# SCH_sweeping-mesuring-device_V2_2022-12-.net
KiCad netlist of a schematic drawn in EasyEDA
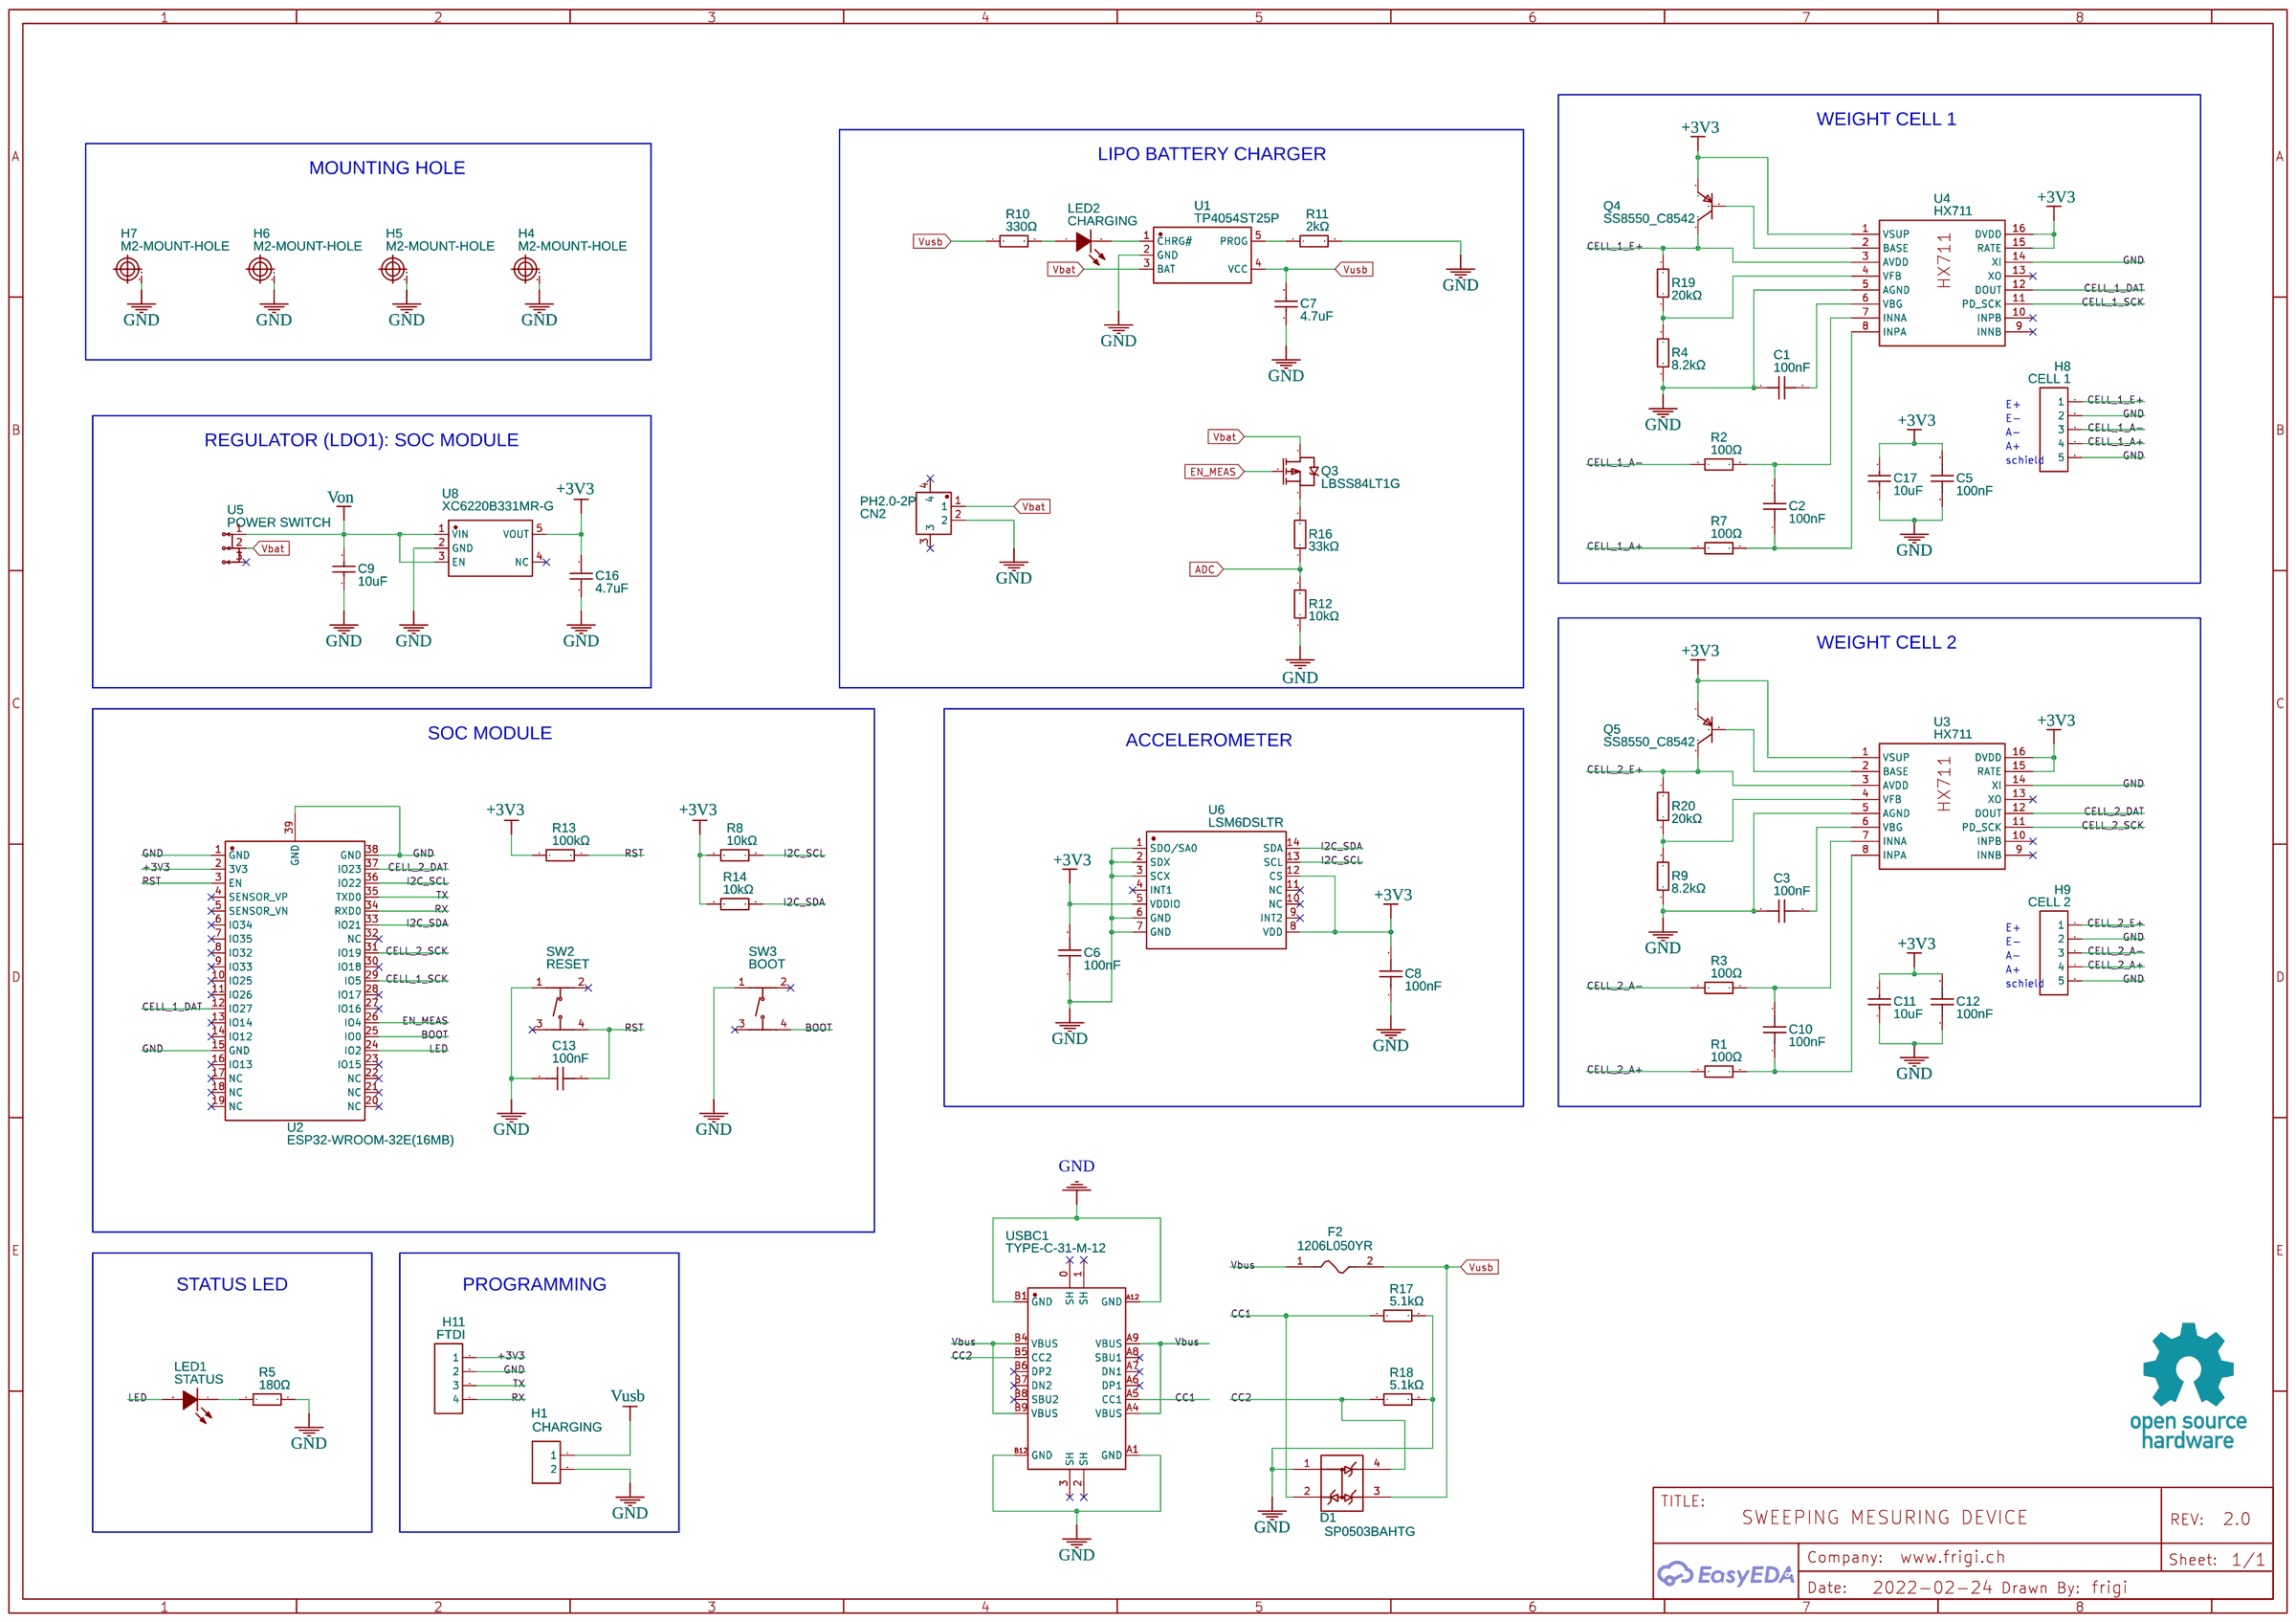
[diagram p0: schematic sheet]

(export (version "E")
  (design (tool "Eeschema 10.0.6"))
  (components
    (comp (ref "C1")
      (value "100nF")
      (fields
        (field (name "BOM_Manufacturer Part") "CC0603KRX7R9BB104")
        (field (name "BOM_Supplier Part") "C14663")
      )
      (libsource (lib "") (part "CC0603KRX7R9BB104_1"))
    )
    (comp (ref "C2")
      (value "100nF")
      (fields
        (field (name "BOM_Manufacturer Part") "CC0603KRX7R9BB104")
        (field (name "BOM_Supplier Part") "C14663")
      )
      (libsource (lib "") (part "CC0603KRX7R9BB104"))
    )
    (comp (ref "C3")
      (value "100nF")
      (fields
        (field (name "BOM_Manufacturer Part") "CC0603KRX7R9BB104")
        (field (name "BOM_Supplier Part") "C14663")
      )
      (libsource (lib "") (part "CC0603KRX7R9BB104_1"))
    )
    (comp (ref "C5")
      (value "100nF")
      (fields
        (field (name "BOM_Manufacturer Part") "CC0603KRX7R9BB104")
        (field (name "BOM_Supplier Part") "C14663")
      )
      (libsource (lib "") (part "CC0603KRX7R9BB104"))
    )
    (comp (ref "C6")
      (value "100nF")
      (fields
        (field (name "BOM_Manufacturer Part") "CC0603KRX7R9BB104")
        (field (name "BOM_Supplier Part") "C14663")
      )
      (libsource (lib "") (part "CC0603KRX7R9BB104"))
    )
    (comp (ref "C7")
      (value "4.7uF")
      (fields
        (field (name "BOM_Manufacturer Part") "CL21A475KAQNNNE")
        (field (name "BOM_Supplier Part") "C1779")
      )
      (libsource (lib "") (part "CL21A475KAQNNNE"))
    )
    (comp (ref "C8")
      (value "100nF")
      (fields
        (field (name "BOM_Manufacturer Part") "CC0603KRX7R9BB104")
        (field (name "BOM_Supplier Part") "C14663")
      )
      (libsource (lib "") (part "CC0603KRX7R9BB104"))
    )
    (comp (ref "C9")
      (value "10uF")
      (fields
        (field (name "BOM_Manufacturer Part") "CL21A106KAYNNNE")
        (field (name "BOM_Supplier Part") "C15850")
      )
      (libsource (lib "") (part "CL21A106KAYNNNE"))
    )
    (comp (ref "C10")
      (value "100nF")
      (fields
        (field (name "BOM_Manufacturer Part") "CC0603KRX7R9BB104")
        (field (name "BOM_Supplier Part") "C14663")
      )
      (libsource (lib "") (part "CC0603KRX7R9BB104"))
    )
    (comp (ref "C11")
      (value "10uF")
      (fields
        (field (name "BOM_Manufacturer Part") "CL21A106KAYNNNE")
        (field (name "BOM_Supplier Part") "C15850")
      )
      (libsource (lib "") (part "CL21A106KAYNNNE"))
    )
    (comp (ref "C12")
      (value "100nF")
      (fields
        (field (name "BOM_Manufacturer Part") "CC0603KRX7R9BB104")
        (field (name "BOM_Supplier Part") "C14663")
      )
      (libsource (lib "") (part "CC0603KRX7R9BB104"))
    )
    (comp (ref "C13")
      (value "100nF")
      (fields
        (field (name "BOM_Manufacturer Part") "CC0603KRX7R9BB104")
        (field (name "BOM_Supplier Part") "C14663")
      )
      (libsource (lib "") (part "CC0603KRX7R9BB104_1"))
    )
    (comp (ref "C16")
      (value "4.7uF")
      (fields
        (field (name "BOM_Manufacturer Part") "CL21A475KAQNNNE")
        (field (name "BOM_Supplier Part") "C1779")
      )
      (libsource (lib "") (part "CL21A475KAQNNNE"))
    )
    (comp (ref "C17")
      (value "10uF")
      (fields
        (field (name "BOM_Manufacturer Part") "CL21A106KAYNNNE")
        (field (name "BOM_Supplier Part") "C15850")
      )
      (libsource (lib "") (part "CL21A106KAYNNNE"))
    )
    (comp (ref "CN2")
      (value "PH2.0-2P")
      (fields (field (name "BOM_Supplier Part") "C64658"))
      (libsource (lib "") (part "PH2.0-2P"))
    )
    (comp (ref "D1")
      (value "SP0503BAHTG")
      (fields (field (name "BOM_Supplier Part") "C7074"))
      (libsource (lib "") (part "SP0503BAHTG"))
    )
    (comp (ref "F2")
      (value "1206L050YR")
      (fields (field (name "BOM_Manufacturer Part") "nSMD050") (field (name "BOM_Supplier Part") "C69688"))
      (libsource (lib "") (part "nSMD050"))
    )
    (comp (ref "H1")
      (value "CHARGING")
      (fields (field (name "BOM_Supplier Part") "C49661"))
      (libsource (lib "") (part "HDR-F-2.54_1x2"))
    )
    (comp (ref "H4") (value "M2-MOUNT-HOLE") (libsource (lib "") (part "M2-MOUNT-HOLE")))
    (comp (ref "H5") (value "M2-MOUNT-HOLE") (libsource (lib "") (part "M2-MOUNT-HOLE")))
    (comp (ref "H6") (value "M2-MOUNT-HOLE") (libsource (lib "") (part "M2-MOUNT-HOLE")))
    (comp (ref "H7") (value "M2-MOUNT-HOLE") (libsource (lib "") (part "M2-MOUNT-HOLE")))
    (comp (ref "H8")
      (value "CELL 1")
      (fields (field (name "BOM_Supplier Part") "C50950"))
      (libsource (lib "") (part "HDR-F-2.54_1x5"))
    )
    (comp (ref "H9")
      (value "CELL 2")
      (fields (field (name "BOM_Supplier Part") "C50950"))
      (libsource (lib "") (part "HDR-F-2.54_1x5"))
    )
    (comp (ref "H11")
      (value "FTDI")
      (fields (field (name "BOM_Supplier Part") "C225501"))
      (libsource (lib "") (part "HDR-F-2.54_1x4"))
    )
    (comp (ref "LED1")
      (value "STATUS")
      (fields
        (field (name "BOM_Manufacturer Part") "KT-0805黄灯 (SMT业务专用)")
        (field (name "BOM_Supplier Part") "C2296")
      )
      (libsource (lib "") (part "17-21SUYC/TR8"))
    )
    (comp (ref "LED2")
      (value "CHARGING")
      (fields
        (field (name "BOM_Manufacturer Part") "KT-0805黄灯 (SMT业务专用)")
        (field (name "BOM_Supplier Part") "C2296")
      )
      (libsource (lib "") (part "17-21SUYC/TR8"))
    )
    (comp (ref "Q3")
      (value "LBSS84LT1G")
      (fields (field (name "BOM_Supplier Part") "C8492"))
      (libsource (lib "") (part "LBSS84LT1G"))
    )
    (comp (ref "Q4")
      (value "SS8550_C8542")
      (fields (field (name "BOM_Manufacturer Part") "SS8550 Y2") (field (name "BOM_Supplier Part") "C8542"))
      (libsource (lib "") (part "SS8550_C8542"))
    )
    (comp (ref "Q5")
      (value "SS8550_C8542")
      (fields (field (name "BOM_Manufacturer Part") "SS8550 Y2") (field (name "BOM_Supplier Part") "C8542"))
      (libsource (lib "") (part "SS8550_C8542"))
    )
    (comp (ref "R1")
      (value "100Ω")
      (fields
        (field (name "BOM_Manufacturer Part") "0402WGF1000TCE")
        (field (name "BOM_Supplier Part") "C25076")
      )
      (libsource (lib "") (part "0402WGF1000TCE"))
    )
    (comp (ref "R2")
      (value "100Ω")
      (fields
        (field (name "BOM_Manufacturer Part") "0402WGF1000TCE")
        (field (name "BOM_Supplier Part") "C25076")
      )
      (libsource (lib "") (part "0402WGF1000TCE"))
    )
    (comp (ref "R3")
      (value "100Ω")
      (fields
        (field (name "BOM_Manufacturer Part") "0402WGF1000TCE")
        (field (name "BOM_Supplier Part") "C25076")
      )
      (libsource (lib "") (part "0402WGF1000TCE"))
    )
    (comp (ref "R4")
      (value "8.2kΩ")
      (fields
        (field (name "BOM_Manufacturer Part") "0603WAF8201T5E")
        (field (name "BOM_Supplier Part") "C25981")
      )
      (libsource (lib "") (part "0603WAF8201T5E"))
    )
    (comp (ref "R5")
      (value "180Ω")
      (fields
        (field (name "BOM_Manufacturer Part") "0603WAF1800T5E")
        (field (name "BOM_Supplier Part") "C22828")
      )
      (libsource (lib "") (part "0603WAF1800T5E"))
    )
    (comp (ref "R7")
      (value "100Ω")
      (fields
        (field (name "BOM_Manufacturer Part") "0402WGF1000TCE")
        (field (name "BOM_Supplier Part") "C25076")
      )
      (libsource (lib "") (part "0402WGF1000TCE"))
    )
    (comp (ref "R8")
      (value "10kΩ")
      (fields
        (field (name "BOM_Manufacturer Part") "0603WAF1002T5E")
        (field (name "BOM_Supplier Part") "C25804")
      )
      (libsource (lib "") (part "0603WAF1002T5E"))
    )
    (comp (ref "R9")
      (value "8.2kΩ")
      (fields
        (field (name "BOM_Manufacturer Part") "0603WAF8201T5E")
        (field (name "BOM_Supplier Part") "C25981")
      )
      (libsource (lib "") (part "0603WAF8201T5E"))
    )
    (comp (ref "R10")
      (value "330Ω")
      (fields
        (field (name "BOM_Manufacturer Part") "0603WAF3300T5E")
        (field (name "BOM_Supplier Part") "C23138")
      )
      (libsource (lib "") (part "0603WAF3300T5E"))
    )
    (comp (ref "R11")
      (value "2kΩ")
      (fields
        (field (name "BOM_Manufacturer Part") "0603WAF2001T5E")
        (field (name "BOM_Supplier Part") "C22975")
      )
      (libsource (lib "") (part "0603WAF2001T5E"))
    )
    (comp (ref "R12")
      (value "10kΩ")
      (fields
        (field (name "BOM_Manufacturer Part") "0603WAF1002T5E")
        (field (name "BOM_Supplier Part") "C25804")
      )
      (libsource (lib "") (part "0603WAF1002T5E_1"))
    )
    (comp (ref "R13")
      (value "100kΩ")
      (fields
        (field (name "BOM_Manufacturer Part") "0603WAF1003T5E")
        (field (name "BOM_Supplier Part") "C25803")
      )
      (libsource (lib "") (part "0603WAF1003T5E"))
    )
    (comp (ref "R14")
      (value "10kΩ")
      (fields
        (field (name "BOM_Manufacturer Part") "0603WAF1002T5E")
        (field (name "BOM_Supplier Part") "C25804")
      )
      (libsource (lib "") (part "0603WAF1002T5E"))
    )
    (comp (ref "R16")
      (value "33kΩ")
      (fields
        (field (name "BOM_Manufacturer Part") "0603WAF3302T5E")
        (field (name "BOM_Supplier Part") "C4216")
      )
      (libsource (lib "") (part "0603WAF3302T5E"))
    )
    (comp (ref "R17")
      (value "5.1kΩ")
      (fields
        (field (name "BOM_Manufacturer Part") "0603WAF5101T5E")
        (field (name "BOM_Supplier Part") "C23186")
      )
      (libsource (lib "") (part "0603WAF5101T5E"))
    )
    (comp (ref "R18")
      (value "5.1kΩ")
      (fields
        (field (name "BOM_Manufacturer Part") "0603WAF5101T5E")
        (field (name "BOM_Supplier Part") "C23186")
      )
      (libsource (lib "") (part "0603WAF5101T5E"))
    )
    (comp (ref "R19")
      (value "20kΩ")
      (fields
        (field (name "BOM_Manufacturer Part") "0603WAF2002T5E")
        (field (name "BOM_Supplier Part") "C4184")
      )
      (libsource (lib "") (part "0603WAF2002T5E"))
    )
    (comp (ref "R20")
      (value "20kΩ")
      (fields
        (field (name "BOM_Manufacturer Part") "0603WAF2002T5E")
        (field (name "BOM_Supplier Part") "C4184")
      )
      (libsource (lib "") (part "0603WAF2002T5E"))
    )
    (comp (ref "SW2")
      (value "RESET")
      (fields
        (field (name "BOM_Manufacturer Part") "TS-1187A-B-A-B")
        (field (name "BOM_Supplier Part") "C318884")
      )
      (libsource (lib "") (part "TS-1187A-B-A-B"))
    )
    (comp (ref "SW3")
      (value "BOOT")
      (fields
        (field (name "BOM_Manufacturer Part") "TS-1187A-B-A-B")
        (field (name "BOM_Supplier Part") "C318884")
      )
      (libsource (lib "") (part "TS-1187A-B-A-B"))
    )
    (comp (ref "U1")
      (value "TP4054ST25P")
      (fields
        (field (name "BOM_Manufacturer Part") "TP4054ST25K")
        (field (name "BOM_Supplier Part") "C382138")
      )
      (libsource (lib "") (part "TP4054ST25P"))
    )
    (comp (ref "U2")
      (value "ESP32-WROOM-32E(16MB)")
      (fields (field (name "BOM_Supplier Part") "C701343"))
      (libsource (lib "") (part "ESP32-WROOM-32E(16MB)"))
    )
    (comp (ref "U3")
      (value "HX711")
      (fields (field (name "BOM_Supplier Part") "C43656"))
      (libsource (lib "") (part "HX711"))
    )
    (comp (ref "U4")
      (value "HX711")
      (fields (field (name "BOM_Supplier Part") "C43656"))
      (libsource (lib "") (part "HX711"))
    )
    (comp (ref "U5")
      (value "POWER SWITCH")
      (fields
        (field (name "BOM_Manufacturer Part") "SS-12D01-G3")
        (field (name "BOM_Supplier Part") "C2998803")
      )
      (libsource (lib "") (part "SS-12D01-G3_C2998803"))
    )
    (comp (ref "U6")
      (value "LSM6DSLTR")
      (fields (field (name "BOM_Supplier Part") "C126672"))
      (libsource (lib "") (part "LSM6DSLTR"))
    )
    (comp (ref "U8")
      (value "XC6220B331MR-G")
      (fields
        (field (name "BOM_Manufacturer Part") "RT9080-33GJ5")
        (field (name "BOM_Supplier Part") "C841192")
      )
      (libsource (lib "") (part "RT9080-33GJ5"))
    )
    (comp (ref "USBC1")
      (value "TYPE-C-31-M-12")
      (fields (field (name "BOM_Supplier Part") "C165948"))
      (libsource (lib "") (part "TYPE-C-31-M-12"))
    )
  )
  (nets
    (net (code "1") (name "+3V3") (class "Default")
      (node (ref "C11") (pin "2") (pinfunction "2_2") (pintype "input"))
      (node (ref "C12") (pin "2") (pinfunction "2_2") (pintype "unspecified"))
      (node (ref "C16") (pin "2") (pinfunction "2_2") (pintype "input"))
      (node (ref "C17") (pin "2") (pinfunction "2_2") (pintype "input"))
      (node (ref "C5") (pin "2") (pinfunction "2_2") (pintype "unspecified"))
      (node (ref "C6") (pin "2") (pinfunction "2_2") (pintype "unspecified"))
      (node (ref "C8") (pin "2") (pinfunction "2_2") (pintype "unspecified"))
      (node (ref "H11") (pin "1") (pinfunction "1_1") (pintype "unspecified"))
      (node (ref "Q4") (pin "2") (pinfunction "E_2") (pintype "unspecified"))
      (node (ref "Q5") (pin "2") (pinfunction "E_2") (pintype "unspecified"))
      (node (ref "R13") (pin "1") (pinfunction "1_1") (pintype "input"))
      (node (ref "R14") (pin "2") (pinfunction "2_2") (pintype "input"))
      (node (ref "R8") (pin "2") (pinfunction "2_2") (pintype "input"))
      (node (ref "U2") (pin "2") (pinfunction "3V3_2") (pintype "unspecified"))
      (node (ref "U3") (pin "1") (pinfunction "VSUP_1") (pintype "unspecified"))
      (node (ref "U3") (pin "15") (pinfunction "RATE_15") (pintype "unspecified"))
      (node (ref "U3") (pin "16") (pinfunction "DVDD_16") (pintype "unspecified"))
      (node (ref "U4") (pin "1") (pinfunction "VSUP_1") (pintype "unspecified"))
      (node (ref "U4") (pin "15") (pinfunction "RATE_15") (pintype "unspecified"))
      (node (ref "U4") (pin "16") (pinfunction "DVDD_16") (pintype "unspecified"))
      (node (ref "U6") (pin "12") (pinfunction "CS_12") (pintype "unspecified"))
      (node (ref "U6") (pin "5") (pinfunction "VDDIO_5") (pintype "unspecified"))
      (node (ref "U6") (pin "8") (pinfunction "VDD_8") (pintype "unspecified"))
      (node (ref "U8") (pin "5") (pinfunction "VOUT_5") (pintype "unspecified"))
    )
    (net (code "2") (name "/BOOT") (class "Default")
      (node (ref "SW3") (pin "4") (pinfunction "D_4") (pintype "unspecified"))
      (node (ref "U2") (pin "25") (pinfunction "IO0_25") (pintype "unspecified"))
    )
    (net (code "3") (name "/CC1") (class "Default")
      (node (ref "D1") (pin "2") (pinfunction "2_2") (pintype "input"))
      (node (ref "R17") (pin "1") (pinfunction "1_1") (pintype "input"))
      (node (ref "USBC1") (pin "A5") (pinfunction "CC1_A5") (pintype "unspecified"))
    )
    (net (code "4") (name "/CC2") (class "Default")
      (node (ref "D1") (pin "4") (pinfunction "4_4") (pintype "input"))
      (node (ref "R18") (pin "1") (pinfunction "1_1") (pintype "input"))
      (node (ref "USBC1") (pin "B5") (pinfunction "CC2_B5") (pintype "unspecified"))
    )
    (net (code "5") (name "/CELL_1_A+") (class "Default")
      (node (ref "H8") (pin "4") (pinfunction "4_4") (pintype "unspecified"))
      (node (ref "R7") (pin "1") (pinfunction "1_1") (pintype "input"))
    )
    (net (code "6") (name "/CELL_1_A-") (class "Default")
      (node (ref "H8") (pin "3") (pinfunction "3_3") (pintype "unspecified"))
      (node (ref "R2") (pin "1") (pinfunction "1_1") (pintype "input"))
    )
    (net (code "7") (name "/CELL_1_DAT") (class "Default")
      (node (ref "U2") (pin "12") (pinfunction "IO27_12") (pintype "unspecified"))
      (node (ref "U4") (pin "12") (pinfunction "DOUT_12") (pintype "unspecified"))
    )
    (net (code "8") (name "/CELL_1_E+") (class "Default")
      (node (ref "H8") (pin "1") (pinfunction "1_1") (pintype "unspecified"))
      (node (ref "Q4") (pin "3") (pinfunction "C_3") (pintype "unspecified"))
      (node (ref "R19") (pin "2") (pinfunction "2_2") (pintype "input"))
      (node (ref "U4") (pin "3") (pinfunction "AVDD_3") (pintype "unspecified"))
    )
    (net (code "9") (name "/CELL_1_SCK") (class "Default")
      (node (ref "U2") (pin "29") (pinfunction "IO5_29") (pintype "unspecified"))
      (node (ref "U4") (pin "11") (pinfunction "PD_SCK_11") (pintype "unspecified"))
    )
    (net (code "10") (name "/CELL_2_A+") (class "Default")
      (node (ref "H9") (pin "4") (pinfunction "4_4") (pintype "unspecified"))
      (node (ref "R1") (pin "1") (pinfunction "1_1") (pintype "input"))
    )
    (net (code "11") (name "/CELL_2_A-") (class "Default")
      (node (ref "H9") (pin "3") (pinfunction "3_3") (pintype "unspecified"))
      (node (ref "R3") (pin "1") (pinfunction "1_1") (pintype "input"))
    )
    (net (code "12") (name "/CELL_2_DAT") (class "Default")
      (node (ref "U2") (pin "37") (pinfunction "IO23_37") (pintype "unspecified"))
      (node (ref "U3") (pin "12") (pinfunction "DOUT_12") (pintype "unspecified"))
    )
    (net (code "13") (name "/CELL_2_E+") (class "Default")
      (node (ref "H9") (pin "1") (pinfunction "1_1") (pintype "unspecified"))
      (node (ref "Q5") (pin "3") (pinfunction "C_3") (pintype "unspecified"))
      (node (ref "R20") (pin "2") (pinfunction "2_2") (pintype "input"))
      (node (ref "U3") (pin "3") (pinfunction "AVDD_3") (pintype "unspecified"))
    )
    (net (code "14") (name "/CELL_2_SCK") (class "Default")
      (node (ref "U2") (pin "31") (pinfunction "IO19_31") (pintype "unspecified"))
      (node (ref "U3") (pin "11") (pinfunction "PD_SCK_11") (pintype "unspecified"))
    )
    (net (code "15") (name "/I2C_SCL") (class "Default")
      (node (ref "R8") (pin "1") (pinfunction "1_1") (pintype "input"))
      (node (ref "U2") (pin "36") (pinfunction "IO22_36") (pintype "unspecified"))
      (node (ref "U6") (pin "13") (pinfunction "SCL_13") (pintype "unspecified"))
    )
    (net (code "16") (name "/I2C_SDA") (class "Default")
      (node (ref "R14") (pin "1") (pinfunction "1_1") (pintype "input"))
      (node (ref "U2") (pin "33") (pinfunction "IO21_33") (pintype "unspecified"))
      (node (ref "U6") (pin "14") (pinfunction "SDA_14") (pintype "unspecified"))
    )
    (net (code "17") (name "/LED") (class "Default")
      (node (ref "LED1") (pin "2") (pinfunction "+_2") (pintype "unspecified"))
      (node (ref "U2") (pin "24") (pinfunction "IO2_24") (pintype "unspecified"))
    )
    (net (code "18") (name "/RST") (class "Default")
      (node (ref "C13") (pin "2") (pinfunction "2_2") (pintype "unspecified"))
      (node (ref "R13") (pin "2") (pinfunction "2_2") (pintype "input"))
      (node (ref "SW2") (pin "4") (pinfunction "D_4") (pintype "unspecified"))
      (node (ref "U2") (pin "3") (pinfunction "EN_3") (pintype "unspecified"))
    )
    (net (code "19") (name "/RX") (class "Default")
      (node (ref "H11") (pin "4") (pinfunction "4_4") (pintype "unspecified"))
      (node (ref "U2") (pin "34") (pinfunction "RXD0_34") (pintype "unspecified"))
    )
    (net (code "20") (name "/TX") (class "Default")
      (node (ref "H11") (pin "3") (pinfunction "3_3") (pintype "unspecified"))
      (node (ref "U2") (pin "35") (pinfunction "TXD0_35") (pintype "unspecified"))
    )
    (net (code "21") (name "/Vbus") (class "Default")
      (node (ref "F2") (pin "1") (pinfunction "1_1") (pintype "unspecified"))
      (node (ref "USBC1") (pin "A4") (pinfunction "VBUS_A4") (pintype "unspecified"))
      (node (ref "USBC1") (pin "A9") (pinfunction "VBUS_A9") (pintype "unspecified"))
      (node (ref "USBC1") (pin "B4") (pinfunction "VBUS_B4") (pintype "unspecified"))
      (node (ref "USBC1") (pin "B9") (pinfunction "VBUS_B9") (pintype "unspecified"))
    )
    (net (code "22") (name "ADC") (class "Default")
      (node (ref "R12") (pin "2") (pinfunction "2_2") (pintype "input"))
      (node (ref "R16") (pin "1") (pinfunction "1_1") (pintype "input"))
    )
    (net (code "23") (name "EN_MEAS") (class "Default")
      (node (ref "Q3") (pin "1") (pinfunction "G_1") (pintype "unspecified"))
      (node (ref "U2") (pin "26") (pinfunction "IO4_26") (pintype "unspecified"))
    )
    (net (code "24") (name "GND") (class "Default")
      (node (ref "C1") (pin "1") (pinfunction "1_1") (pintype "unspecified"))
      (node (ref "C11") (pin "1") (pinfunction "1_1") (pintype "input"))
      (node (ref "C12") (pin "1") (pinfunction "1_1") (pintype "unspecified"))
      (node (ref "C13") (pin "1") (pinfunction "1_1") (pintype "unspecified"))
      (node (ref "C16") (pin "1") (pinfunction "1_1") (pintype "input"))
      (node (ref "C17") (pin "1") (pinfunction "1_1") (pintype "input"))
      (node (ref "C3") (pin "1") (pinfunction "1_1") (pintype "unspecified"))
      (node (ref "C5") (pin "1") (pinfunction "1_1") (pintype "unspecified"))
      (node (ref "C6") (pin "1") (pinfunction "1_1") (pintype "unspecified"))
      (node (ref "C7") (pin "1") (pinfunction "1_1") (pintype "input"))
      (node (ref "C8") (pin "1") (pinfunction "1_1") (pintype "unspecified"))
      (node (ref "C9") (pin "1") (pinfunction "1_1") (pintype "input"))
      (node (ref "CN2") (pin "2") (pinfunction "2_2") (pintype "unspecified"))
      (node (ref "D1") (pin "1") (pinfunction "1_1") (pintype "input"))
      (node (ref "H1") (pin "2") (pinfunction "2_2") (pintype "input"))
      (node (ref "H11") (pin "2") (pinfunction "2_2") (pintype "unspecified"))
      (node (ref "H4") (pin "1") (pinfunction "GND_1") (pintype "passive"))
      (node (ref "H5") (pin "1") (pinfunction "GND_1") (pintype "passive"))
      (node (ref "H6") (pin "1") (pinfunction "GND_1") (pintype "passive"))
      (node (ref "H7") (pin "1") (pinfunction "GND_1") (pintype "passive"))
      (node (ref "H8") (pin "2") (pinfunction "2_2") (pintype "unspecified"))
      (node (ref "H8") (pin "5") (pinfunction "5_5") (pintype "unspecified"))
      (node (ref "H9") (pin "2") (pinfunction "2_2") (pintype "unspecified"))
      (node (ref "H9") (pin "5") (pinfunction "5_5") (pintype "unspecified"))
      (node (ref "R11") (pin "2") (pinfunction "2_2") (pintype "input"))
      (node (ref "R12") (pin "1") (pinfunction "1_1") (pintype "input"))
      (node (ref "R17") (pin "2") (pinfunction "2_2") (pintype "input"))
      (node (ref "R18") (pin "2") (pinfunction "2_2") (pintype "input"))
      (node (ref "R4") (pin "1") (pinfunction "1_1") (pintype "input"))
      (node (ref "R5") (pin "2") (pinfunction "2_2") (pintype "input"))
      (node (ref "R9") (pin "1") (pinfunction "1_1") (pintype "input"))
      (node (ref "SW2") (pin "1") (pinfunction "A_1") (pintype "unspecified"))
      (node (ref "SW3") (pin "1") (pinfunction "A_1") (pintype "unspecified"))
      (node (ref "U1") (pin "2") (pinfunction "GND_2") (pintype "unspecified"))
      (node (ref "U2") (pin "1") (pinfunction "GND_1") (pintype "unspecified"))
      (node (ref "U2") (pin "15") (pinfunction "GND_15") (pintype "unspecified"))
      (node (ref "U2") (pin "38") (pinfunction "GND_38") (pintype "unspecified"))
      (node (ref "U2") (pin "39") (pinfunction "GND_39") (pintype "unspecified"))
      (node (ref "U3") (pin "14") (pinfunction "XI_14") (pintype "unspecified"))
      (node (ref "U3") (pin "5") (pinfunction "AGND_5") (pintype "unspecified"))
      (node (ref "U4") (pin "14") (pinfunction "XI_14") (pintype "unspecified"))
      (node (ref "U4") (pin "5") (pinfunction "AGND_5") (pintype "unspecified"))
      (node (ref "U6") (pin "1") (pinfunction "SDO/SA0_1") (pintype "unspecified"))
      (node (ref "U6") (pin "2") (pinfunction "SDX_2") (pintype "unspecified"))
      (node (ref "U6") (pin "3") (pinfunction "SCX_3") (pintype "unspecified"))
      (node (ref "U6") (pin "6") (pinfunction "GND_6") (pintype "unspecified"))
      (node (ref "U6") (pin "7") (pinfunction "GND_7") (pintype "unspecified"))
      (node (ref "U8") (pin "2") (pinfunction "GND_2") (pintype "unspecified"))
      (node (ref "USBC1") (pin "A1") (pinfunction "GND_A1") (pintype "unspecified"))
      (node (ref "USBC1") (pin "A12") (pinfunction "GND_A12") (pintype "unspecified"))
      (node (ref "USBC1") (pin "B1") (pinfunction "GND_B1") (pintype "unspecified"))
      (node (ref "USBC1") (pin "B12") (pinfunction "GND_B12") (pintype "unspecified"))
    )
    (net (code "25") (name "Net-(LED1--)") (class "Default")
      (node (ref "LED1") (pin "1") (pinfunction "-_1") (pintype "unspecified"))
      (node (ref "R5") (pin "1") (pinfunction "1_1") (pintype "input"))
    )
    (net (code "26") (name "Net-(LED2-+)") (class "Default")
      (node (ref "LED2") (pin "2") (pinfunction "+_2") (pintype "unspecified"))
      (node (ref "R10") (pin "2") (pinfunction "2_2") (pintype "input"))
    )
    (net (code "27") (name "Net-(LED2--)") (class "Default")
      (node (ref "LED2") (pin "1") (pinfunction "-_1") (pintype "unspecified"))
      (node (ref "U1") (pin "1") (pinfunction "CHRG#_1") (pintype "unspecified"))
    )
    (net (code "28") (name "Net-(Q3-S)") (class "Default")
      (node (ref "Q3") (pin "2") (pinfunction "S_2") (pintype "unspecified"))
      (node (ref "R16") (pin "2") (pinfunction "2_2") (pintype "input"))
    )
    (net (code "29") (name "Net-(Q4-B)") (class "Default")
      (node (ref "Q4") (pin "1") (pinfunction "B_1") (pintype "unspecified"))
      (node (ref "U4") (pin "2") (pinfunction "BASE_2") (pintype "unspecified"))
    )
    (net (code "30") (name "Net-(Q5-B)") (class "Default")
      (node (ref "Q5") (pin "1") (pinfunction "B_1") (pintype "unspecified"))
      (node (ref "U3") (pin "2") (pinfunction "BASE_2") (pintype "unspecified"))
    )
    (net (code "31") (name "Net-(U1-PROG)") (class "Default")
      (node (ref "R11") (pin "1") (pinfunction "1_1") (pintype "input"))
      (node (ref "U1") (pin "5") (pinfunction "PROG_5") (pintype "unspecified"))
    )
    (net (code "32") (name "Net-(U3-INNA)") (class "Default")
      (node (ref "C10") (pin "2") (pinfunction "2_2") (pintype "unspecified"))
      (node (ref "R3") (pin "2") (pinfunction "2_2") (pintype "input"))
      (node (ref "U3") (pin "7") (pinfunction "INNA_7") (pintype "unspecified"))
    )
    (net (code "33") (name "Net-(U3-INPA)") (class "Default")
      (node (ref "C10") (pin "1") (pinfunction "1_1") (pintype "unspecified"))
      (node (ref "R1") (pin "2") (pinfunction "2_2") (pintype "input"))
      (node (ref "U3") (pin "8") (pinfunction "INPA_8") (pintype "unspecified"))
    )
    (net (code "34") (name "Net-(U3-VBG)") (class "Default")
      (node (ref "C3") (pin "2") (pinfunction "2_2") (pintype "unspecified"))
      (node (ref "U3") (pin "6") (pinfunction "VBG_6") (pintype "unspecified"))
    )
    (net (code "35") (name "Net-(U3-VFB)") (class "Default")
      (node (ref "R20") (pin "1") (pinfunction "1_1") (pintype "input"))
      (node (ref "R9") (pin "2") (pinfunction "2_2") (pintype "input"))
      (node (ref "U3") (pin "4") (pinfunction "VFB_4") (pintype "unspecified"))
    )
    (net (code "36") (name "Net-(U4-INNA)") (class "Default")
      (node (ref "C2") (pin "2") (pinfunction "2_2") (pintype "unspecified"))
      (node (ref "R2") (pin "2") (pinfunction "2_2") (pintype "input"))
      (node (ref "U4") (pin "7") (pinfunction "INNA_7") (pintype "unspecified"))
    )
    (net (code "37") (name "Net-(U4-INPA)") (class "Default")
      (node (ref "C2") (pin "1") (pinfunction "1_1") (pintype "unspecified"))
      (node (ref "R7") (pin "2") (pinfunction "2_2") (pintype "input"))
      (node (ref "U4") (pin "8") (pinfunction "INPA_8") (pintype "unspecified"))
    )
    (net (code "38") (name "Net-(U4-VBG)") (class "Default")
      (node (ref "C1") (pin "2") (pinfunction "2_2") (pintype "unspecified"))
      (node (ref "U4") (pin "6") (pinfunction "VBG_6") (pintype "unspecified"))
    )
    (net (code "39") (name "Net-(U4-VFB)") (class "Default")
      (node (ref "R19") (pin "1") (pinfunction "1_1") (pintype "input"))
      (node (ref "R4") (pin "2") (pinfunction "2_2") (pintype "input"))
      (node (ref "U4") (pin "4") (pinfunction "VFB_4") (pintype "unspecified"))
    )
    (net (code "40") (name "Vbat") (class "Default")
      (node (ref "CN2") (pin "1") (pinfunction "1_1") (pintype "unspecified"))
      (node (ref "Q3") (pin "3") (pinfunction "D_3") (pintype "unspecified"))
      (node (ref "U1") (pin "3") (pinfunction "BAT_3") (pintype "unspecified"))
      (node (ref "U5") (pin "2") (pinfunction "2_2") (pintype "unspecified"))
    )
    (net (code "41") (name "Von") (class "Default")
      (node (ref "C9") (pin "2") (pinfunction "2_2") (pintype "input"))
      (node (ref "U5") (pin "1") (pinfunction "1_1") (pintype "unspecified"))
      (node (ref "U8") (pin "1") (pinfunction "VIN_1") (pintype "unspecified"))
      (node (ref "U8") (pin "3") (pinfunction "EN_3") (pintype "unspecified"))
    )
    (net (code "42") (name "Vusb") (class "Default")
      (node (ref "C7") (pin "2") (pinfunction "2_2") (pintype "input"))
      (node (ref "D1") (pin "3") (pinfunction "3_3") (pintype "input"))
      (node (ref "F2") (pin "2") (pinfunction "2_2") (pintype "unspecified"))
      (node (ref "H1") (pin "1") (pinfunction "1_1") (pintype "input"))
      (node (ref "R10") (pin "1") (pinfunction "1_1") (pintype "input"))
      (node (ref "U1") (pin "4") (pinfunction "VCC_4") (pintype "unspecified"))
    )
    (net (code "43") (name "unconnected-(CN2-Pad3)") (class "Default")
      (node (ref "CN2") (pin "3") (pinfunction "3_3") (pintype "unspecified+no_connect"))
    )
    (net (code "44") (name "unconnected-(CN2-Pad4)") (class "Default")
      (node (ref "CN2") (pin "4") (pinfunction "4_4") (pintype "unspecified+no_connect"))
    )
    (net (code "45") (name "unconnected-(SW2-B-Pad2)") (class "Default")
      (node (ref "SW2") (pin "2") (pinfunction "B_2") (pintype "unspecified+no_connect"))
    )
    (net (code "46") (name "unconnected-(SW2-C-Pad3)") (class "Default")
      (node (ref "SW2") (pin "3") (pinfunction "C_3") (pintype "unspecified+no_connect"))
    )
    (net (code "47") (name "unconnected-(SW3-B-Pad2)") (class "Default")
      (node (ref "SW3") (pin "2") (pinfunction "B_2") (pintype "unspecified+no_connect"))
    )
    (net (code "48") (name "unconnected-(SW3-C-Pad3)") (class "Default")
      (node (ref "SW3") (pin "3") (pinfunction "C_3") (pintype "unspecified+no_connect"))
    )
    (net (code "49") (name "unconnected-(U2-IO12-Pad14)") (class "Default")
      (node (ref "U2") (pin "14") (pinfunction "IO12_14") (pintype "unspecified+no_connect"))
    )
    (net (code "50") (name "unconnected-(U2-IO13-Pad16)") (class "Default")
      (node (ref "U2") (pin "16") (pinfunction "IO13_16") (pintype "unspecified+no_connect"))
    )
    (net (code "51") (name "unconnected-(U2-IO14-Pad13)") (class "Default")
      (node (ref "U2") (pin "13") (pinfunction "IO14_13") (pintype "unspecified+no_connect"))
    )
    (net (code "52") (name "unconnected-(U2-IO15-Pad23)") (class "Default")
      (node (ref "U2") (pin "23") (pinfunction "IO15_23") (pintype "unspecified+no_connect"))
    )
    (net (code "53") (name "unconnected-(U2-IO16-Pad27)") (class "Default")
      (node (ref "U2") (pin "27") (pinfunction "IO16_27") (pintype "unspecified+no_connect"))
    )
    (net (code "54") (name "unconnected-(U2-IO17-Pad28)") (class "Default")
      (node (ref "U2") (pin "28") (pinfunction "IO17_28") (pintype "unspecified+no_connect"))
    )
    (net (code "55") (name "unconnected-(U2-IO18-Pad30)") (class "Default")
      (node (ref "U2") (pin "30") (pinfunction "IO18_30") (pintype "unspecified+no_connect"))
    )
    (net (code "56") (name "unconnected-(U2-IO25-Pad10)") (class "Default")
      (node (ref "U2") (pin "10") (pinfunction "IO25_10") (pintype "unspecified+no_connect"))
    )
    (net (code "57") (name "unconnected-(U2-IO26-Pad11)") (class "Default")
      (node (ref "U2") (pin "11") (pinfunction "IO26_11") (pintype "unspecified+no_connect"))
    )
    (net (code "58") (name "unconnected-(U2-IO32-Pad8)") (class "Default")
      (node (ref "U2") (pin "8") (pinfunction "IO32_8") (pintype "unspecified+no_connect"))
    )
    (net (code "59") (name "unconnected-(U2-IO33-Pad9)") (class "Default")
      (node (ref "U2") (pin "9") (pinfunction "IO33_9") (pintype "unspecified+no_connect"))
    )
    (net (code "60") (name "unconnected-(U2-IO34-Pad6)") (class "Default")
      (node (ref "U2") (pin "6") (pinfunction "IO34_6") (pintype "unspecified+no_connect"))
    )
    (net (code "61") (name "unconnected-(U2-IO35-Pad7)") (class "Default")
      (node (ref "U2") (pin "7") (pinfunction "IO35_7") (pintype "unspecified+no_connect"))
    )
    (net (code "62") (name "unconnected-(U2-NC-Pad17)") (class "Default")
      (node (ref "U2") (pin "17") (pinfunction "NC_17") (pintype "unspecified+no_connect"))
    )
    (net (code "63") (name "unconnected-(U2-NC-Pad18)") (class "Default")
      (node (ref "U2") (pin "18") (pinfunction "NC_18") (pintype "unspecified+no_connect"))
    )
    (net (code "64") (name "unconnected-(U2-NC-Pad19)") (class "Default")
      (node (ref "U2") (pin "19") (pinfunction "NC_19") (pintype "unspecified+no_connect"))
    )
    (net (code "65") (name "unconnected-(U2-NC-Pad20)") (class "Default")
      (node (ref "U2") (pin "20") (pinfunction "NC_20") (pintype "unspecified+no_connect"))
    )
    (net (code "66") (name "unconnected-(U2-NC-Pad21)") (class "Default")
      (node (ref "U2") (pin "21") (pinfunction "NC_21") (pintype "unspecified+no_connect"))
    )
    (net (code "67") (name "unconnected-(U2-NC-Pad22)") (class "Default")
      (node (ref "U2") (pin "22") (pinfunction "NC_22") (pintype "unspecified+no_connect"))
    )
    (net (code "68") (name "unconnected-(U2-NC-Pad32)") (class "Default")
      (node (ref "U2") (pin "32") (pinfunction "NC_32") (pintype "unspecified+no_connect"))
    )
    (net (code "69") (name "unconnected-(U2-SENSOR_VN-Pad5)") (class "Default")
      (node (ref "U2") (pin "5") (pinfunction "SENSOR_VN_5") (pintype "unspecified+no_connect"))
    )
    (net (code "70") (name "unconnected-(U2-SENSOR_VP-Pad4)") (class "Default")
      (node (ref "U2") (pin "4") (pinfunction "SENSOR_VP_4") (pintype "unspecified+no_connect"))
    )
    (net (code "71") (name "unconnected-(U3-INNB-Pad9)") (class "Default")
      (node (ref "U3") (pin "9") (pinfunction "INNB_9") (pintype "unspecified+no_connect"))
    )
    (net (code "72") (name "unconnected-(U3-INPB-Pad10)") (class "Default")
      (node (ref "U3") (pin "10") (pinfunction "INPB_10") (pintype "unspecified+no_connect"))
    )
    (net (code "73") (name "unconnected-(U3-XO-Pad13)") (class "Default")
      (node (ref "U3") (pin "13") (pinfunction "XO_13") (pintype "unspecified+no_connect"))
    )
    (net (code "74") (name "unconnected-(U4-INNB-Pad9)") (class "Default")
      (node (ref "U4") (pin "9") (pinfunction "INNB_9") (pintype "unspecified+no_connect"))
    )
    (net (code "75") (name "unconnected-(U4-INPB-Pad10)") (class "Default")
      (node (ref "U4") (pin "10") (pinfunction "INPB_10") (pintype "unspecified+no_connect"))
    )
    (net (code "76") (name "unconnected-(U4-XO-Pad13)") (class "Default")
      (node (ref "U4") (pin "13") (pinfunction "XO_13") (pintype "unspecified+no_connect"))
    )
    (net (code "77") (name "unconnected-(U5-Pad3)") (class "Default")
      (node (ref "U5") (pin "3") (pinfunction "3_3") (pintype "unspecified+no_connect"))
    )
    (net (code "78") (name "unconnected-(U6-INT1-Pad4)") (class "Default")
      (node (ref "U6") (pin "4") (pinfunction "INT1_4") (pintype "unspecified+no_connect"))
    )
    (net (code "79") (name "unconnected-(U6-INT2-Pad9)") (class "Default")
      (node (ref "U6") (pin "9") (pinfunction "INT2_9") (pintype "unspecified+no_connect"))
    )
    (net (code "80") (name "unconnected-(U6-NC-Pad10)") (class "Default")
      (node (ref "U6") (pin "10") (pinfunction "NC_10") (pintype "unspecified+no_connect"))
    )
    (net (code "81") (name "unconnected-(U6-NC-Pad11)") (class "Default")
      (node (ref "U6") (pin "11") (pinfunction "NC_11") (pintype "unspecified+no_connect"))
    )
    (net (code "82") (name "unconnected-(U8-NC-Pad4)") (class "Default")
      (node (ref "U8") (pin "4") (pinfunction "NC_4") (pintype "unspecified+no_connect"))
    )
    (net (code "83") (name "unconnected-(USBC1-DN1-PadA7)") (class "Default")
      (node (ref "USBC1") (pin "A7") (pinfunction "DN1_A7") (pintype "unspecified+no_connect"))
    )
    (net (code "84") (name "unconnected-(USBC1-DN2-PadB7)") (class "Default")
      (node (ref "USBC1") (pin "B7") (pinfunction "DN2_B7") (pintype "unspecified+no_connect"))
    )
    (net (code "85") (name "unconnected-(USBC1-DP1-PadA6)") (class "Default")
      (node (ref "USBC1") (pin "A6") (pinfunction "DP1_A6") (pintype "unspecified+no_connect"))
    )
    (net (code "86") (name "unconnected-(USBC1-DP2-PadB6)") (class "Default")
      (node (ref "USBC1") (pin "B6") (pinfunction "DP2_B6") (pintype "unspecified+no_connect"))
    )
    (net (code "87") (name "unconnected-(USBC1-SBU1-PadA8)") (class "Default")
      (node (ref "USBC1") (pin "A8") (pinfunction "SBU1_A8") (pintype "unspecified+no_connect"))
    )
    (net (code "88") (name "unconnected-(USBC1-SBU2-PadB8)") (class "Default")
      (node (ref "USBC1") (pin "B8") (pinfunction "SBU2_B8") (pintype "unspecified+no_connect"))
    )
    (net (code "89") (name "unconnected-(USBC1-SH-Pad0)") (class "Default")
      (node (ref "USBC1") (pin "0") (pinfunction "SH_0") (pintype "unspecified+no_connect"))
    )
    (net (code "90") (name "unconnected-(USBC1-SH-Pad1)") (class "Default")
      (node (ref "USBC1") (pin "1") (pinfunction "SH_1") (pintype "unspecified+no_connect"))
    )
    (net (code "91") (name "unconnected-(USBC1-SH-Pad2)") (class "Default")
      (node (ref "USBC1") (pin "2") (pinfunction "SH_2") (pintype "unspecified+no_connect"))
    )
    (net (code "92") (name "unconnected-(USBC1-SH-Pad3)") (class "Default")
      (node (ref "USBC1") (pin "3") (pinfunction "SH_3") (pintype "unspecified+no_connect"))
    )
  )
)
